# DCconverter.net
KiCad netlist of a schematic drawn in Altium Designer
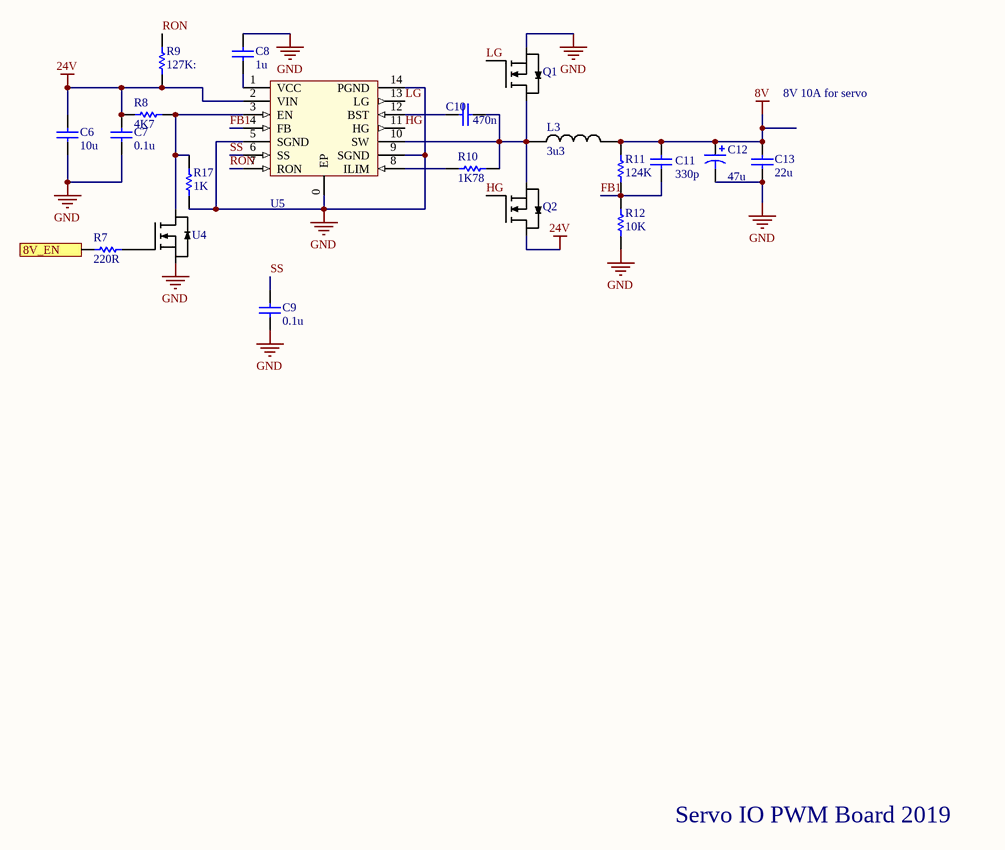
[diagram p0: DCconverter.SchDoc]

(export (version "E")
  (design (tool "Eeschema 10.0.6"))
  (components
    (comp (ref "C6")
      (value "10u")
      (footprint "CAPC2012X135N")
      (description "Capacitor")
      (fields (field (name "Comment") "Cap") (field (name "PUBLISHER") "Altium Limited"))
      (libsource (lib "IOBoard_Low") (part "Cap"))
    )
    (comp (ref "C7")
      (value "0.1u")
      (footprint "CAPC1608X90N")
      (description "Capacitor")
      (fields (field (name "Comment") "Cap") (field (name "PUBLISHER") "Altium Limited"))
      (libsource (lib "IOBoard_Low") (part "Cap"))
    )
    (comp (ref "C8")
      (value "1u")
      (footprint "CAPC1608X90N")
      (description "Capacitor")
      (fields (field (name "Comment") "Cap") (field (name "PUBLISHER") "Altium Limited"))
      (libsource (lib "IOBoard_Low") (part "Cap"))
    )
    (comp (ref "C9")
      (value "0.1u")
      (footprint "CAPC1608X90N")
      (description "Capacitor")
      (fields (field (name "Comment") "Cap") (field (name "PUBLISHER") "Altium Limited"))
      (libsource (lib "IOBoard_Low") (part "Cap"))
    )
    (comp (ref "C10")
      (value "470n")
      (footprint "CAPC2012X135N")
      (description "Capacitor")
      (fields (field (name "Comment") "Cap") (field (name "PUBLISHER") "Altium Limited"))
      (libsource (lib "IOBoard_Low") (part "Cap"))
    )
    (comp (ref "C11")
      (value "330p")
      (footprint "CAPC1608X90N")
      (description "Capacitor")
      (fields (field (name "Comment") "Cap") (field (name "PUBLISHER") "Altium Limited"))
      (libsource (lib "IOBoard_Low") (part "Cap"))
    )
    (comp (ref "C12")
      (value "47u")
      (footprint "CAP_ELEC_SIZE_E")
      (description "Polarized Capacitor (Radial)")
      (fields (field (name "Comment") "Cap Pol1") (field (name "PUBLISHER") "Altium Limited"))
      (libsource (lib "Miscellaneous Devices") (part "Cap Pol1"))
    )
    (comp (ref "C13")
      (value "22u")
      (footprint "CAPC3216X100N")
      (description "Capacitor")
      (fields (field (name "Comment") "Cap") (field (name "PUBLISHER") "Altium Limited"))
      (libsource (lib "IOBoard_Low") (part "Cap"))
    )
    (comp (ref "L3")
      (value "3.3uH 8A sat.")
      (footprint "IND_7x7x3")
      (description "3.3uH inductor SMD. 8-12A Sat. Current")
      (fields (field (name "INDUCTANCE") "3u3"))
      (libsource (lib "IOBoard_Low") (part "SRP6030CA-3R3M"))
    )
    (comp (ref "Q1")
      (value "60V N-Channel MOSFET")
      (footprint "SON_5x6_NexFET")
      (description "60V N-Channel NexFET Power MOSFET. 14A minimum depending on temperature")
      (libsource (lib "IOBoard_Low") (part "CSD18534Q5A"))
    )
    (comp (ref "Q2")
      (value "60V N-Channel MOSFET")
      (footprint "SON_5x6_NexFET")
      (description "60V N-Channel NexFET Power MOSFET. 14A minimum depending on temperature")
      (libsource (lib "IOBoard_Low") (part "CSD18534Q5A"))
    )
    (comp (ref "R7")
      (value "220R")
      (footprint "RESC1608X55N")
      (description "Resistor")
      (fields (field (name "Comment") "Res1") (field (name "PUBLISHER") "Altium Limited"))
      (libsource (lib "IOBoard_Low") (part "Res1"))
    )
    (comp (ref "R8")
      (value "4K7")
      (footprint "RESC1608X55N")
      (description "Resistor")
      (fields (field (name "Comment") "Res1") (field (name "PUBLISHER") "Altium Limited"))
      (libsource (lib "IOBoard_Low") (part "Res1"))
    )
    (comp (ref "R9")
      (value "127K:")
      (footprint "RESC1608X55N")
      (description "Resistor")
      (fields (field (name "Comment") "Res1") (field (name "PUBLISHER") "Altium Limited"))
      (libsource (lib "IOBoard_Low") (part "Res1"))
    )
    (comp (ref "R10")
      (value "1K78")
      (footprint "RESC1608X55N")
      (description "Resistor")
      (fields (field (name "Comment") "Res1") (field (name "PUBLISHER") "Altium Limited"))
      (libsource (lib "IOBoard_Low") (part "Res1"))
    )
    (comp (ref "R11")
      (value "124K")
      (footprint "RESC1608X55N")
      (description "Resistor")
      (fields (field (name "Comment") "Res1") (field (name "PUBLISHER") "Altium Limited"))
      (libsource (lib "IOBoard_Low") (part "Res1"))
    )
    (comp (ref "R12")
      (value "10K")
      (footprint "RESC1608X55N")
      (description "Resistor")
      (fields (field (name "Comment") "Res1") (field (name "PUBLISHER") "Altium Limited"))
      (libsource (lib "IOBoard_Low") (part "Res1"))
    )
    (comp (ref "R17")
      (value "1K")
      (footprint "RESC1608X55N")
      (description "Resistor")
      (fields (field (name "Comment") "Res1") (field (name "PUBLISHER") "Altium Limited"))
      (libsource (lib "IOBoard_Low") (part "Res1"))
    )
    (comp (ref "U4")
      (value "Enhancing mode mosfet")
      (footprint "SOT323")
      (description "Small N channel MOSFET as a level shifter.")
      (libsource (lib "IOBoard_Low") (part "DMN63D8LW-13"))
    )
    (comp (ref "U5")
      (value "LM3150 buck converter")
      (footprint "HTSSOP14")
      (libsource (lib "IOBoard_Low") (part "LM3150"))
    )
  )
  (nets
    (net (code "1") (name "/8V_EN") (class "Default")
      (node (ref "R7") (pin "1") (pinfunction "1_1") (pintype "passive"))
    )
    (net (code "2") (name "/FB1") (class "Default")
      (node (ref "C11") (pin "1") (pinfunction "1_1") (pintype "passive"))
      (node (ref "R11") (pin "1") (pinfunction "1_1") (pintype "passive"))
      (node (ref "R12") (pin "2") (pinfunction "2_2") (pintype "passive"))
      (node (ref "U5") (pin "4") (pinfunction "FB_4") (pintype "input"))
    )
    (net (code "3") (name "/HG") (class "Default")
      (node (ref "Q2") (pin "1") (pinfunction "G_1") (pintype "passive"))
      (node (ref "U5") (pin "11") (pinfunction "HG_11") (pintype "output"))
    )
    (net (code "4") (name "/LG") (class "Default")
      (node (ref "Q1") (pin "1") (pinfunction "G_1") (pintype "passive"))
      (node (ref "U5") (pin "13") (pinfunction "LG_13") (pintype "output"))
    )
    (net (code "5") (name "/RON") (class "Default")
      (node (ref "R9") (pin "2") (pinfunction "2_2") (pintype "passive"))
      (node (ref "U5") (pin "7") (pinfunction "RON_7") (pintype "input"))
    )
    (net (code "6") (name "/SS") (class "Default")
      (node (ref "C9") (pin "2") (pinfunction "2_2") (pintype "passive"))
      (node (ref "U5") (pin "6") (pinfunction "SS_6") (pintype "input"))
    )
    (net (code "7") (name "8V") (class "Default")
      (node (ref "C11") (pin "2") (pinfunction "2_2") (pintype "passive"))
      (node (ref "C12") (pin "1") (pinfunction "1_1") (pintype "passive"))
      (node (ref "C13") (pin "2") (pinfunction "2_2") (pintype "passive"))
      (node (ref "L3") (pin "2") (pinfunction "2_2") (pintype "power_in"))
      (node (ref "R11") (pin "2") (pinfunction "2_2") (pintype "passive"))
    )
    (net (code "8") (name "24V") (class "Default")
      (node (ref "C6") (pin "2") (pinfunction "2_2") (pintype "passive"))
      (node (ref "C7") (pin "2") (pinfunction "2_2") (pintype "passive"))
      (node (ref "Q2") (pin "4") (pinfunction "D_4") (pintype "passive"))
      (node (ref "R8") (pin "1") (pinfunction "1_1") (pintype "passive"))
      (node (ref "R9") (pin "1") (pinfunction "1_1") (pintype "passive"))
      (node (ref "U5") (pin "2") (pinfunction "VIN_2") (pintype "power_in"))
    )
    (net (code "9") (name "GND") (class "Default")
      (node (ref "C12") (pin "2") (pinfunction "2_2") (pintype "passive"))
      (node (ref "C13") (pin "1") (pinfunction "1_1") (pintype "passive"))
      (node (ref "C6") (pin "1") (pinfunction "1_1") (pintype "passive"))
      (node (ref "C7") (pin "1") (pinfunction "1_1") (pintype "passive"))
      (node (ref "C8") (pin "2") (pinfunction "2_2") (pintype "passive"))
      (node (ref "C9") (pin "1") (pinfunction "1_1") (pintype "passive"))
      (node (ref "Q1") (pin "3") (pinfunction "S_3") (pintype "passive"))
      (node (ref "R12") (pin "1") (pinfunction "1_1") (pintype "passive"))
      (node (ref "R17") (pin "1") (pinfunction "1_1") (pintype "passive"))
      (node (ref "U4") (pin "2") (pinfunction "S_2") (pintype "passive"))
      (node (ref "U5") (pin "0") (pinfunction "EP_0") (pintype "power_in"))
      (node (ref "U5") (pin "14") (pinfunction "PGND_14") (pintype "power_in"))
      (node (ref "U5") (pin "5") (pinfunction "SGND_5") (pintype "power_in"))
      (node (ref "U5") (pin "9") (pinfunction "SGND_9") (pintype "power_in"))
    )
    (net (code "10") (name "Net-(Q1-D)") (class "Default")
      (node (ref "C10") (pin "2") (pinfunction "2_2") (pintype "passive"))
      (node (ref "L3") (pin "1") (pinfunction "1_1") (pintype "power_in"))
      (node (ref "Q1") (pin "4") (pinfunction "D_4") (pintype "passive"))
      (node (ref "Q2") (pin "3") (pinfunction "S_3") (pintype "passive"))
      (node (ref "R10") (pin "2") (pinfunction "2_2") (pintype "passive"))
      (node (ref "U5") (pin "10") (pinfunction "SW_10") (pintype "power_in"))
    )
    (net (code "11") (name "Net-(U4-D)") (class "Default")
      (node (ref "R17") (pin "2") (pinfunction "2_2") (pintype "passive"))
      (node (ref "R8") (pin "2") (pinfunction "2_2") (pintype "passive"))
      (node (ref "U4") (pin "3") (pinfunction "D_3") (pintype "passive"))
      (node (ref "U5") (pin "3") (pinfunction "EN_3") (pintype "input"))
    )
    (net (code "12") (name "Net-(U4-G)") (class "Default")
      (node (ref "R7") (pin "2") (pinfunction "2_2") (pintype "passive"))
      (node (ref "U4") (pin "1") (pinfunction "G_1") (pintype "passive"))
    )
    (net (code "13") (name "Net-(U5-BST)") (class "Default")
      (node (ref "C10") (pin "1") (pinfunction "1_1") (pintype "passive"))
      (node (ref "U5") (pin "12") (pinfunction "BST_12") (pintype "input"))
    )
    (net (code "14") (name "Net-(U5-ILIM)") (class "Default")
      (node (ref "R10") (pin "1") (pinfunction "1_1") (pintype "passive"))
      (node (ref "U5") (pin "8") (pinfunction "ILIM_8") (pintype "input"))
    )
    (net (code "15") (name "Net-(U5-VCC)") (class "Default")
      (node (ref "C8") (pin "1") (pinfunction "1_1") (pintype "passive"))
      (node (ref "U5") (pin "1") (pinfunction "VCC_1") (pintype "power_in"))
    )
  )
)
